# Battery_Board_v3_0.net
KiCad netlist of a schematic drawn in EAGLE
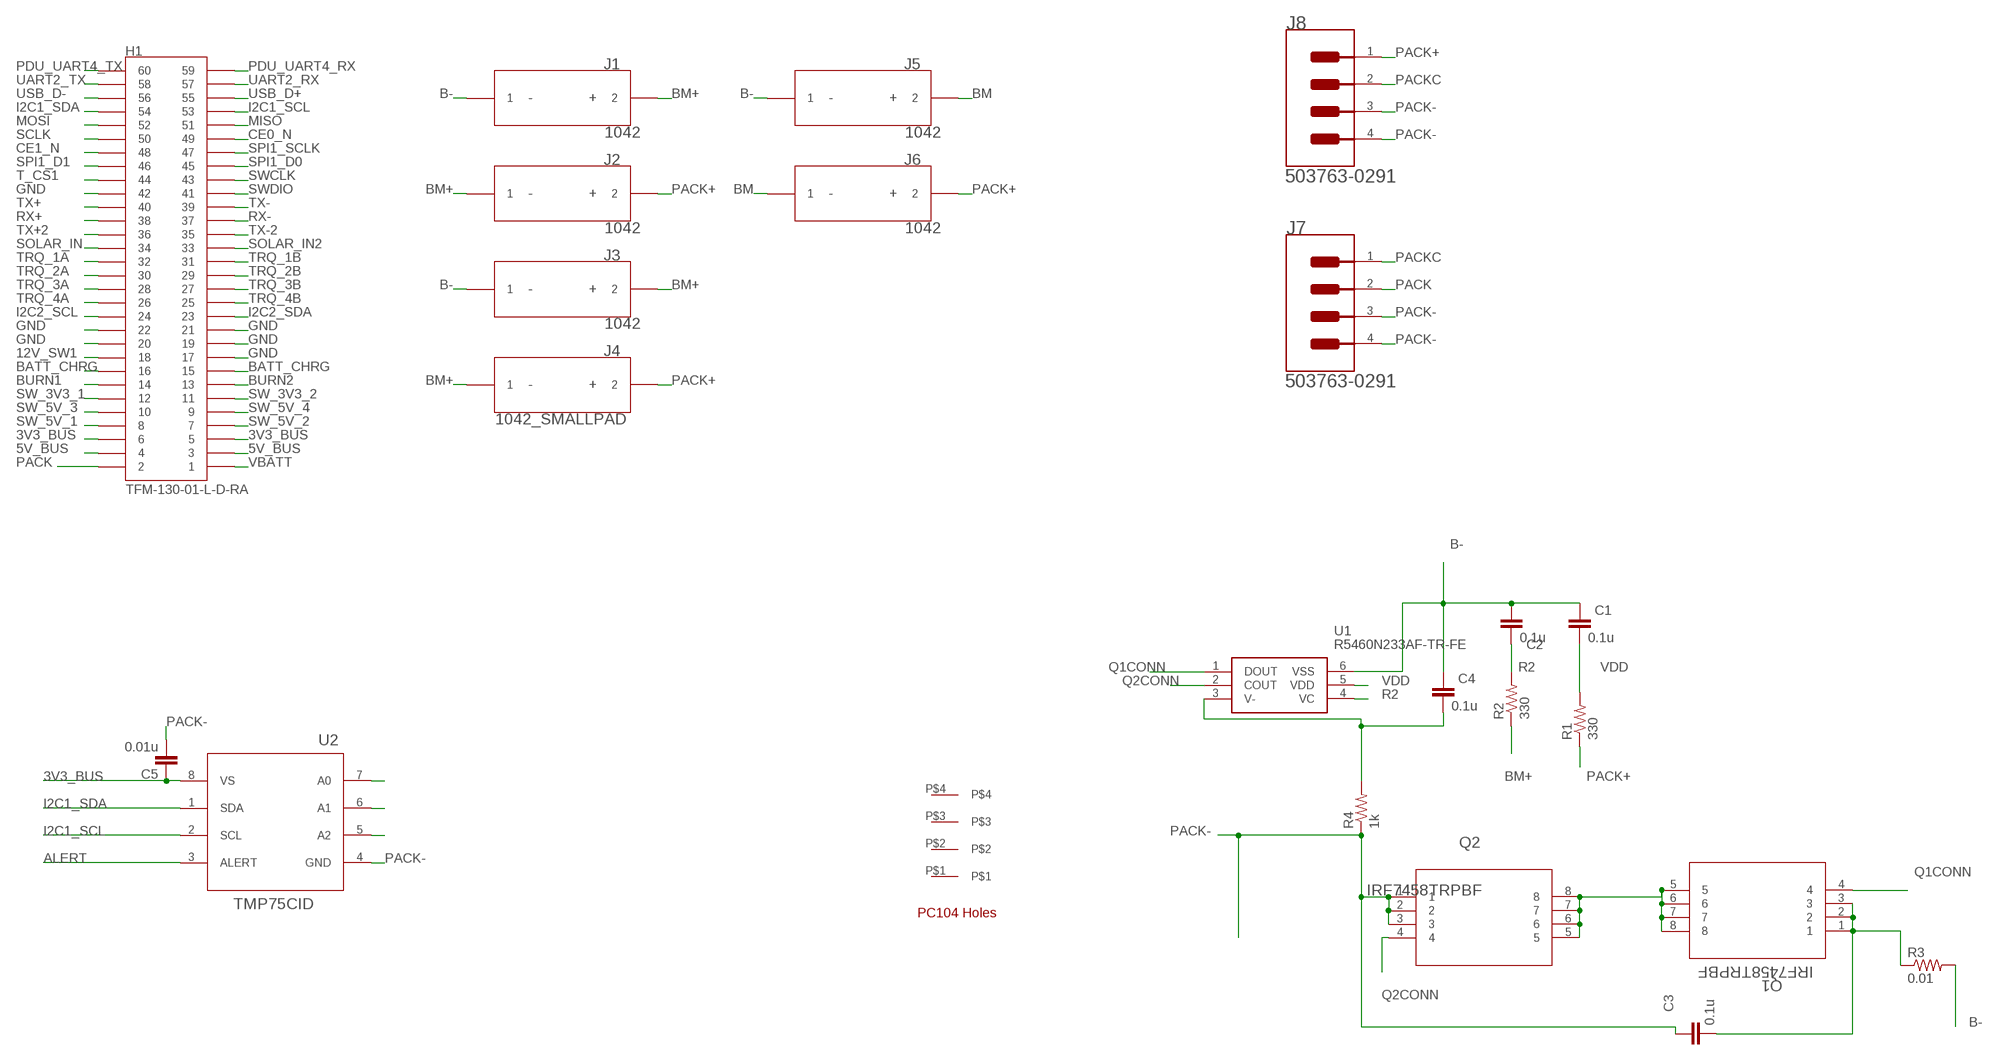
[diagram p0: schematic, sheet 1]

(export (version "E")
  (design (tool "Eeschema 10.0.6"))
  (components
    (comp (ref "C1")
      (value "0.1u")
      (footprint "eagle-import:0603-CAP")
      (libsource (lib "eagle-import") (part "CAP0603-CAP"))
    )
    (comp (ref "C2")
      (value "0.1u")
      (footprint "eagle-import:0603-CAP")
      (libsource (lib "eagle-import") (part "CAP0603-CAP"))
    )
    (comp (ref "C3")
      (value "0.1u")
      (footprint "eagle-import:0603-CAP")
      (libsource (lib "eagle-import") (part "CAP0603-CAP"))
    )
    (comp (ref "C4")
      (value "0.1u")
      (footprint "eagle-import:0603-CAP")
      (libsource (lib "eagle-import") (part "CAP0603-CAP"))
    )
    (comp (ref "C5")
      (value "0.01u")
      (footprint "eagle-import:0805")
      (libsource (lib "eagle-import") (part "CAP0805"))
    )
    (comp (ref "H1")
      (value "TFM-130-01-L-D-RA")
      (footprint "eagle-import:60_PIN")
      (libsource (lib "eagle-import") (part "TFM-130-01-L-D-RA"))
    )
    (comp (ref "J1")
      (value "1042")
      (footprint "eagle-import:1042_KEY")
      (fields (field (name "COPYRIGHT") "Copyright (C) 2021 Ultra Librarian. All rights reserved."))
      (libsource (lib "eagle-import") (part "1042"))
    )
    (comp (ref "J2")
      (value "1042")
      (footprint "eagle-import:1042_KEY")
      (fields (field (name "COPYRIGHT") "Copyright (C) 2021 Ultra Librarian. All rights reserved."))
      (libsource (lib "eagle-import") (part "1042"))
    )
    (comp (ref "J3")
      (value "1042")
      (footprint "eagle-import:1042_KEY")
      (fields (field (name "COPYRIGHT") "Copyright (C) 2021 Ultra Librarian. All rights reserved."))
      (libsource (lib "eagle-import") (part "1042"))
    )
    (comp (ref "J4")
      (value "1042_SMALLPAD")
      (footprint "eagle-import:1042_KEY_SMALLPAD")
      (libsource (lib "eagle-import") (part "1042_SMALLPAD"))
    )
    (comp (ref "J5")
      (value "1042")
      (footprint "eagle-import:1042_KEY")
      (fields (field (name "COPYRIGHT") "Copyright (C) 2021 Ultra Librarian. All rights reserved."))
      (libsource (lib "eagle-import") (part "1042"))
    )
    (comp (ref "J6")
      (value "1042")
      (footprint "eagle-import:1042_KEY")
      (fields (field (name "COPYRIGHT") "Copyright (C) 2021 Ultra Librarian. All rights reserved."))
      (libsource (lib "eagle-import") (part "1042"))
    )
    (comp (ref "J7")
      (value "MOLEX_503763-0291MOLEX_503763-0291_0_0")
      (footprint "eagle-import:MOLEX_503763-0291_0")
      (fields
        (field (name "DIGIKEY_PART_NUMBER") "WM10654CT-ND")
        (field (name "MF") "Molex")
        (field (name "MOUSER_PART_NUMBER") "538-503763-0291")
      )
      (libsource (lib "eagle-import") (part "MOLEX_503763-0291MOLEX_503763-0291_0_0"))
    )
    (comp (ref "J8")
      (value "MOLEX_503763-0291MOLEX_503763-0291_0_0")
      (footprint "eagle-import:MOLEX_503763-0291_0")
      (fields
        (field (name "DIGIKEY_PART_NUMBER") "WM10654CT-ND")
        (field (name "MF") "Molex")
        (field (name "MOUSER_PART_NUMBER") "538-503763-0291")
      )
      (libsource (lib "eagle-import") (part "MOLEX_503763-0291MOLEX_503763-0291_0_0"))
    )
    (comp (ref "Q1")
      (value "IRF7458TRPBF")
      (footprint "eagle-import:SO-8_IRF7458_3P9X4P9_INF")
      (fields (field (name "COPYRIGHT") "Copyright (C) 2021 Ultra Librarian. All rights reserved."))
      (libsource (lib "eagle-import") (part "IRF7458TRPBF"))
    )
    (comp (ref "Q2")
      (value "IRF7458TRPBF")
      (footprint "eagle-import:SO-8_IRF7458_3P9X4P9_INF")
      (fields (field (name "COPYRIGHT") "Copyright (C) 2021 Ultra Librarian. All rights reserved."))
      (libsource (lib "eagle-import") (part "IRF7458TRPBF"))
    )
    (comp (ref "R1")
      (value "330")
      (footprint "eagle-import:0603-RES")
      (libsource (lib "eagle-import") (part "RESISTOR0603-RES"))
    )
    (comp (ref "R2")
      (value "330")
      (footprint "eagle-import:0603-RES")
      (libsource (lib "eagle-import") (part "RESISTOR0603-RES"))
    )
    (comp (ref "R3")
      (value "0.01")
      (footprint "eagle-import:R2512")
      (libsource (lib "eagle-import") (part "RESISTOR2512"))
    )
    (comp (ref "R4")
      (value "1k")
      (footprint "eagle-import:0603-RES")
      (libsource (lib "eagle-import") (part "RESISTOR0603-RES"))
    )
    (comp (ref "U$1")
      (value "PC104_HOLES")
      (footprint "eagle-import:PC104_HOLES")
      (libsource (lib "eagle-import") (part "PC104_HOLES"))
    )
    (comp (ref "U1")
      (value "R5460N233AF-TR-FE")
      (footprint "eagle-import:SOT95P280X140-6N")
      (fields (field (name "MOUSER_PART_NUMBER") "848-R5460N233AFTRFE"))
      (libsource (lib "eagle-import") (part "R5460N233AF-TR-FE"))
    )
    (comp (ref "U2")
      (value "TMP75CID")
      (footprint "eagle-import:D0008A_N")
      (fields (field (name "COPYRIGHT") "Copyright (C) 2023 Ultra Librarian. All rights reserved."))
      (libsource (lib "eagle-import") (part "TMP75CID"))
    )
  )
  (nets
    (net (code "1") (name "/3V3_BUS") (class "Default")
      (node (ref "C5") (pin "1") (pinfunction "1_1") (pintype "passive"))
      (node (ref "H1") (pin "5") (pinfunction "5_5") (pintype "bidirectional"))
      (node (ref "H1") (pin "6") (pinfunction "6_6") (pintype "bidirectional"))
      (node (ref "U2") (pin "8") (pinfunction "VS_8") (pintype "power_in"))
    )
    (net (code "2") (name "/5V_BUS") (class "Default")
      (node (ref "H1") (pin "3") (pinfunction "3_3") (pintype "bidirectional"))
      (node (ref "H1") (pin "4") (pinfunction "4_4") (pintype "bidirectional"))
    )
    (net (code "3") (name "/12V_SW1") (class "Default")
      (node (ref "H1") (pin "18") (pinfunction "18_18") (pintype "bidirectional"))
    )
    (net (code "4") (name "/ALERT") (class "Default")
      (node (ref "U2") (pin "3") (pinfunction "ALERT_3") (pintype "open_collector"))
    )
    (net (code "5") (name "/B-") (class "Default")
      (node (ref "C1") (pin "1") (pinfunction "1_1") (pintype "passive"))
      (node (ref "C2") (pin "1") (pinfunction "1_1") (pintype "passive"))
      (node (ref "C4") (pin "1") (pinfunction "1_1") (pintype "passive"))
      (node (ref "J1") (pin "1") (pinfunction "1_1") (pintype "passive"))
      (node (ref "J3") (pin "1") (pinfunction "1_1") (pintype "passive"))
      (node (ref "J5") (pin "1") (pinfunction "1_1") (pintype "passive"))
      (node (ref "R3") (pin "2") (pinfunction "2_2") (pintype "passive"))
      (node (ref "U1") (pin "6") (pinfunction "VSS_6") (pintype "bidirectional"))
    )
    (net (code "6") (name "/BATT_CHRG") (class "Default")
      (node (ref "H1") (pin "15") (pinfunction "15_15") (pintype "bidirectional"))
      (node (ref "H1") (pin "16") (pinfunction "16_16") (pintype "bidirectional"))
    )
    (net (code "7") (name "/BM") (class "Default")
      (node (ref "J5") (pin "2") (pinfunction "2_2") (pintype "passive"))
      (node (ref "J6") (pin "1") (pinfunction "1_1") (pintype "passive"))
    )
    (net (code "8") (name "/BM+") (class "Default")
      (node (ref "J1") (pin "2") (pinfunction "2_2") (pintype "passive"))
      (node (ref "J2") (pin "1") (pinfunction "1_1") (pintype "passive"))
      (node (ref "J3") (pin "2") (pinfunction "2_2") (pintype "passive"))
      (node (ref "J4") (pin "1") (pinfunction "1_1") (pintype "passive"))
      (node (ref "R2") (pin "1") (pinfunction "1_1") (pintype "passive"))
    )
    (net (code "9") (name "/BURN1") (class "Default")
      (node (ref "H1") (pin "14") (pinfunction "14_14") (pintype "bidirectional"))
    )
    (net (code "10") (name "/BURN2") (class "Default")
      (node (ref "H1") (pin "13") (pinfunction "13_13") (pintype "bidirectional"))
    )
    (net (code "11") (name "/CE0_N") (class "Default")
      (node (ref "H1") (pin "49") (pinfunction "49_49") (pintype "bidirectional"))
    )
    (net (code "12") (name "/CE1_N") (class "Default")
      (node (ref "H1") (pin "48") (pinfunction "48_48") (pintype "bidirectional"))
    )
    (net (code "13") (name "/GND") (class "Default")
      (node (ref "H1") (pin "17") (pinfunction "17_17") (pintype "bidirectional"))
      (node (ref "H1") (pin "19") (pinfunction "19_19") (pintype "bidirectional"))
      (node (ref "H1") (pin "20") (pinfunction "20_20") (pintype "bidirectional"))
      (node (ref "H1") (pin "21") (pinfunction "21_21") (pintype "bidirectional"))
      (node (ref "H1") (pin "22") (pinfunction "22_22") (pintype "bidirectional"))
      (node (ref "H1") (pin "42") (pinfunction "42_42") (pintype "bidirectional"))
    )
    (net (code "14") (name "/I2C1_SCL") (class "Default")
      (node (ref "H1") (pin "53") (pinfunction "53_53") (pintype "bidirectional"))
      (node (ref "U2") (pin "2") (pinfunction "SCL_2") (pintype "input"))
    )
    (net (code "15") (name "/I2C1_SDA") (class "Default")
      (node (ref "H1") (pin "54") (pinfunction "54_54") (pintype "bidirectional"))
      (node (ref "U2") (pin "1") (pinfunction "SDA_1") (pintype "bidirectional"))
    )
    (net (code "16") (name "/I2C2_SCL") (class "Default")
      (node (ref "H1") (pin "24") (pinfunction "24_24") (pintype "bidirectional"))
    )
    (net (code "17") (name "/I2C2_SDA") (class "Default")
      (node (ref "H1") (pin "23") (pinfunction "23_23") (pintype "bidirectional"))
    )
    (net (code "18") (name "/MISO") (class "Default")
      (node (ref "H1") (pin "51") (pinfunction "51_51") (pintype "bidirectional"))
    )
    (net (code "19") (name "/MOSI") (class "Default")
      (node (ref "H1") (pin "52") (pinfunction "52_52") (pintype "bidirectional"))
    )
    (net (code "20") (name "/PACK") (class "Default")
      (node (ref "H1") (pin "2") (pinfunction "2_2") (pintype "bidirectional"))
      (node (ref "J7") (pin "2") (pinfunction "2_2") (pintype "bidirectional"))
    )
    (net (code "21") (name "/PACK+") (class "Default")
      (node (ref "J2") (pin "2") (pinfunction "2_2") (pintype "passive"))
      (node (ref "J4") (pin "2") (pinfunction "2_2") (pintype "passive"))
      (node (ref "J6") (pin "2") (pinfunction "2_2") (pintype "passive"))
      (node (ref "J8") (pin "1") (pinfunction "1_1") (pintype "bidirectional"))
      (node (ref "R1") (pin "1") (pinfunction "1_1") (pintype "passive"))
    )
    (net (code "22") (name "/PACK-") (class "Default")
      (node (ref "C3") (pin "1") (pinfunction "1_1") (pintype "passive"))
      (node (ref "C5") (pin "2") (pinfunction "2_2") (pintype "passive"))
      (node (ref "J7") (pin "3") (pinfunction "MNT_1_3") (pintype "bidirectional"))
      (node (ref "J7") (pin "4") (pinfunction "MNT_2_4") (pintype "bidirectional"))
      (node (ref "J8") (pin "3") (pinfunction "MNT_1_3") (pintype "bidirectional"))
      (node (ref "J8") (pin "4") (pinfunction "MNT_2_4") (pintype "bidirectional"))
      (node (ref "Q2") (pin "1") (pinfunction "1_1") (pintype "passive"))
      (node (ref "Q2") (pin "2") (pinfunction "2_2") (pintype "passive"))
      (node (ref "Q2") (pin "3") (pinfunction "3_3") (pintype "passive"))
      (node (ref "R4") (pin "1") (pinfunction "1_1") (pintype "passive"))
      (node (ref "U2") (pin "4") (pinfunction "GND_4") (pintype "power_in"))
    )
    (net (code "23") (name "/PACKC") (class "Default")
      (node (ref "J7") (pin "1") (pinfunction "1_1") (pintype "bidirectional"))
      (node (ref "J8") (pin "2") (pinfunction "2_2") (pintype "bidirectional"))
    )
    (net (code "24") (name "/PDU_UART4_RX") (class "Default")
      (node (ref "H1") (pin "59") (pinfunction "59_59") (pintype "bidirectional"))
    )
    (net (code "25") (name "/PDU_UART4_TX") (class "Default")
      (node (ref "H1") (pin "60") (pinfunction "60_60") (pintype "bidirectional"))
    )
    (net (code "26") (name "/Q1CONN") (class "Default")
      (node (ref "Q1") (pin "4") (pinfunction "4_4") (pintype "passive"))
      (node (ref "U1") (pin "1") (pinfunction "DOUT_1") (pintype "bidirectional"))
    )
    (net (code "27") (name "/Q2CONN") (class "Default")
      (node (ref "Q2") (pin "4") (pinfunction "4_4") (pintype "passive"))
      (node (ref "U1") (pin "2") (pinfunction "COUT_2") (pintype "bidirectional"))
    )
    (net (code "28") (name "/R2") (class "Default")
      (node (ref "C2") (pin "2") (pinfunction "2_2") (pintype "passive"))
      (node (ref "R2") (pin "2") (pinfunction "2_2") (pintype "passive"))
      (node (ref "U1") (pin "4") (pinfunction "VC_4") (pintype "bidirectional"))
    )
    (net (code "29") (name "/RX+") (class "Default")
      (node (ref "H1") (pin "38") (pinfunction "38_38") (pintype "bidirectional"))
    )
    (net (code "30") (name "/RX-") (class "Default")
      (node (ref "H1") (pin "37") (pinfunction "37_37") (pintype "bidirectional"))
    )
    (net (code "31") (name "/SCLK") (class "Default")
      (node (ref "H1") (pin "50") (pinfunction "50_50") (pintype "bidirectional"))
    )
    (net (code "32") (name "/SOLAR_IN") (class "Default")
      (node (ref "H1") (pin "34") (pinfunction "34_34") (pintype "bidirectional"))
    )
    (net (code "33") (name "/SOLAR_IN2") (class "Default")
      (node (ref "H1") (pin "33") (pinfunction "33_33") (pintype "bidirectional"))
    )
    (net (code "34") (name "/SPI1_D0") (class "Default")
      (node (ref "H1") (pin "45") (pinfunction "45_45") (pintype "bidirectional"))
    )
    (net (code "35") (name "/SPI1_D1") (class "Default")
      (node (ref "H1") (pin "46") (pinfunction "46_46") (pintype "bidirectional"))
    )
    (net (code "36") (name "/SPI1_SCLK") (class "Default")
      (node (ref "H1") (pin "47") (pinfunction "47_47") (pintype "bidirectional"))
    )
    (net (code "37") (name "/SWCLK") (class "Default")
      (node (ref "H1") (pin "43") (pinfunction "43_43") (pintype "bidirectional"))
    )
    (net (code "38") (name "/SWDIO") (class "Default")
      (node (ref "H1") (pin "41") (pinfunction "41_41") (pintype "bidirectional"))
    )
    (net (code "39") (name "/SW_3V3_1") (class "Default")
      (node (ref "H1") (pin "12") (pinfunction "12_12") (pintype "bidirectional"))
    )
    (net (code "40") (name "/SW_3V3_2") (class "Default")
      (node (ref "H1") (pin "11") (pinfunction "11_11") (pintype "bidirectional"))
    )
    (net (code "41") (name "/SW_5V_1") (class "Default")
      (node (ref "H1") (pin "8") (pinfunction "8_8") (pintype "bidirectional"))
    )
    (net (code "42") (name "/SW_5V_2") (class "Default")
      (node (ref "H1") (pin "7") (pinfunction "7_7") (pintype "bidirectional"))
    )
    (net (code "43") (name "/SW_5V_3") (class "Default")
      (node (ref "H1") (pin "10") (pinfunction "10_10") (pintype "bidirectional"))
    )
    (net (code "44") (name "/SW_5V_4") (class "Default")
      (node (ref "H1") (pin "9") (pinfunction "9_9") (pintype "bidirectional"))
    )
    (net (code "45") (name "/TRQ_1A") (class "Default")
      (node (ref "H1") (pin "32") (pinfunction "32_32") (pintype "bidirectional"))
    )
    (net (code "46") (name "/TRQ_1B") (class "Default")
      (node (ref "H1") (pin "31") (pinfunction "31_31") (pintype "bidirectional"))
    )
    (net (code "47") (name "/TRQ_2A") (class "Default")
      (node (ref "H1") (pin "30") (pinfunction "30_30") (pintype "bidirectional"))
    )
    (net (code "48") (name "/TRQ_2B") (class "Default")
      (node (ref "H1") (pin "29") (pinfunction "29_29") (pintype "bidirectional"))
    )
    (net (code "49") (name "/TRQ_3A") (class "Default")
      (node (ref "H1") (pin "28") (pinfunction "28_28") (pintype "bidirectional"))
    )
    (net (code "50") (name "/TRQ_3B") (class "Default")
      (node (ref "H1") (pin "27") (pinfunction "27_27") (pintype "bidirectional"))
    )
    (net (code "51") (name "/TRQ_4A") (class "Default")
      (node (ref "H1") (pin "26") (pinfunction "26_26") (pintype "bidirectional"))
    )
    (net (code "52") (name "/TRQ_4B") (class "Default")
      (node (ref "H1") (pin "25") (pinfunction "25_25") (pintype "bidirectional"))
    )
    (net (code "53") (name "/TX+") (class "Default")
      (node (ref "H1") (pin "40") (pinfunction "40_40") (pintype "bidirectional"))
    )
    (net (code "54") (name "/TX+2") (class "Default")
      (node (ref "H1") (pin "36") (pinfunction "36_36") (pintype "bidirectional"))
    )
    (net (code "55") (name "/TX-") (class "Default")
      (node (ref "H1") (pin "39") (pinfunction "39_39") (pintype "bidirectional"))
    )
    (net (code "56") (name "/TX-2") (class "Default")
      (node (ref "H1") (pin "35") (pinfunction "35_35") (pintype "bidirectional"))
    )
    (net (code "57") (name "/T_CS1") (class "Default")
      (node (ref "H1") (pin "44") (pinfunction "44_44") (pintype "bidirectional"))
    )
    (net (code "58") (name "/UART2_RX") (class "Default")
      (node (ref "H1") (pin "57") (pinfunction "57_57") (pintype "bidirectional"))
    )
    (net (code "59") (name "/UART2_TX") (class "Default")
      (node (ref "H1") (pin "58") (pinfunction "58_58") (pintype "bidirectional"))
    )
    (net (code "60") (name "/USB_D+") (class "Default")
      (node (ref "H1") (pin "55") (pinfunction "55_55") (pintype "bidirectional"))
    )
    (net (code "61") (name "/USB_D-") (class "Default")
      (node (ref "H1") (pin "56") (pinfunction "56_56") (pintype "bidirectional"))
    )
    (net (code "62") (name "/VBATT") (class "Default")
      (node (ref "H1") (pin "1") (pinfunction "1_1") (pintype "bidirectional"))
    )
    (net (code "63") (name "/VDD") (class "Default")
      (node (ref "C1") (pin "2") (pinfunction "2_2") (pintype "passive"))
      (node (ref "R1") (pin "2") (pinfunction "2_2") (pintype "passive"))
      (node (ref "U1") (pin "5") (pinfunction "VDD_5") (pintype "bidirectional"))
    )
    (net (code "64") (name "Net-(C3-Pad2)") (class "Default")
      (node (ref "C3") (pin "2") (pinfunction "2_2") (pintype "passive"))
      (node (ref "Q1") (pin "1") (pinfunction "1_1") (pintype "passive"))
      (node (ref "Q1") (pin "2") (pinfunction "2_2") (pintype "passive"))
      (node (ref "Q1") (pin "3") (pinfunction "3_3") (pintype "passive"))
      (node (ref "R3") (pin "1") (pinfunction "1_1") (pintype "passive"))
    )
    (net (code "65") (name "Net-(Q1-Pad5)") (class "Default")
      (node (ref "Q1") (pin "5") (pinfunction "5_5") (pintype "passive"))
      (node (ref "Q1") (pin "6") (pinfunction "6_6") (pintype "passive"))
      (node (ref "Q1") (pin "7") (pinfunction "7_7") (pintype "passive"))
      (node (ref "Q1") (pin "8") (pinfunction "8_8") (pintype "passive"))
      (node (ref "Q2") (pin "5") (pinfunction "5_5") (pintype "passive"))
      (node (ref "Q2") (pin "6") (pinfunction "6_6") (pintype "passive"))
      (node (ref "Q2") (pin "7") (pinfunction "7_7") (pintype "passive"))
      (node (ref "Q2") (pin "8") (pinfunction "8_8") (pintype "passive"))
    )
    (net (code "66") (name "Net-(U1-V-)") (class "Default")
      (node (ref "C4") (pin "2") (pinfunction "2_2") (pintype "passive"))
      (node (ref "R4") (pin "2") (pinfunction "2_2") (pintype "passive"))
      (node (ref "U1") (pin "3") (pinfunction "V-_3") (pintype "bidirectional"))
    )
    (net (code "67") (name "unconnected-(U$1-PadP$1)") (class "Default")
      (node (ref "U$1") (pin "P$1") (pinfunction "P$1_P$1") (pintype "bidirectional"))
    )
    (net (code "68") (name "unconnected-(U$1-PadP$2)") (class "Default")
      (node (ref "U$1") (pin "P$2") (pinfunction "P$2_P$2") (pintype "bidirectional"))
    )
    (net (code "69") (name "unconnected-(U$1-PadP$3)") (class "Default")
      (node (ref "U$1") (pin "P$3") (pinfunction "P$3_P$3") (pintype "bidirectional"))
    )
    (net (code "70") (name "unconnected-(U$1-PadP$4)") (class "Default")
      (node (ref "U$1") (pin "P$4") (pinfunction "P$4_P$4") (pintype "bidirectional"))
    )
    (net (code "71") (name "unconnected-(U2-A0-Pad7)") (class "Default")
      (node (ref "U2") (pin "7") (pinfunction "A0_7") (pintype "input"))
    )
    (net (code "72") (name "unconnected-(U2-A1-Pad6)") (class "Default")
      (node (ref "U2") (pin "6") (pinfunction "A1_6") (pintype "input"))
    )
    (net (code "73") (name "unconnected-(U2-A2-Pad5)") (class "Default")
      (node (ref "U2") (pin "5") (pinfunction "A2_5") (pintype "input"))
    )
  )
)
